# efm8ub1-kalypso-mezzanine-usb-interface-.net
KiCad netlist of a schematic drawn in EAGLE
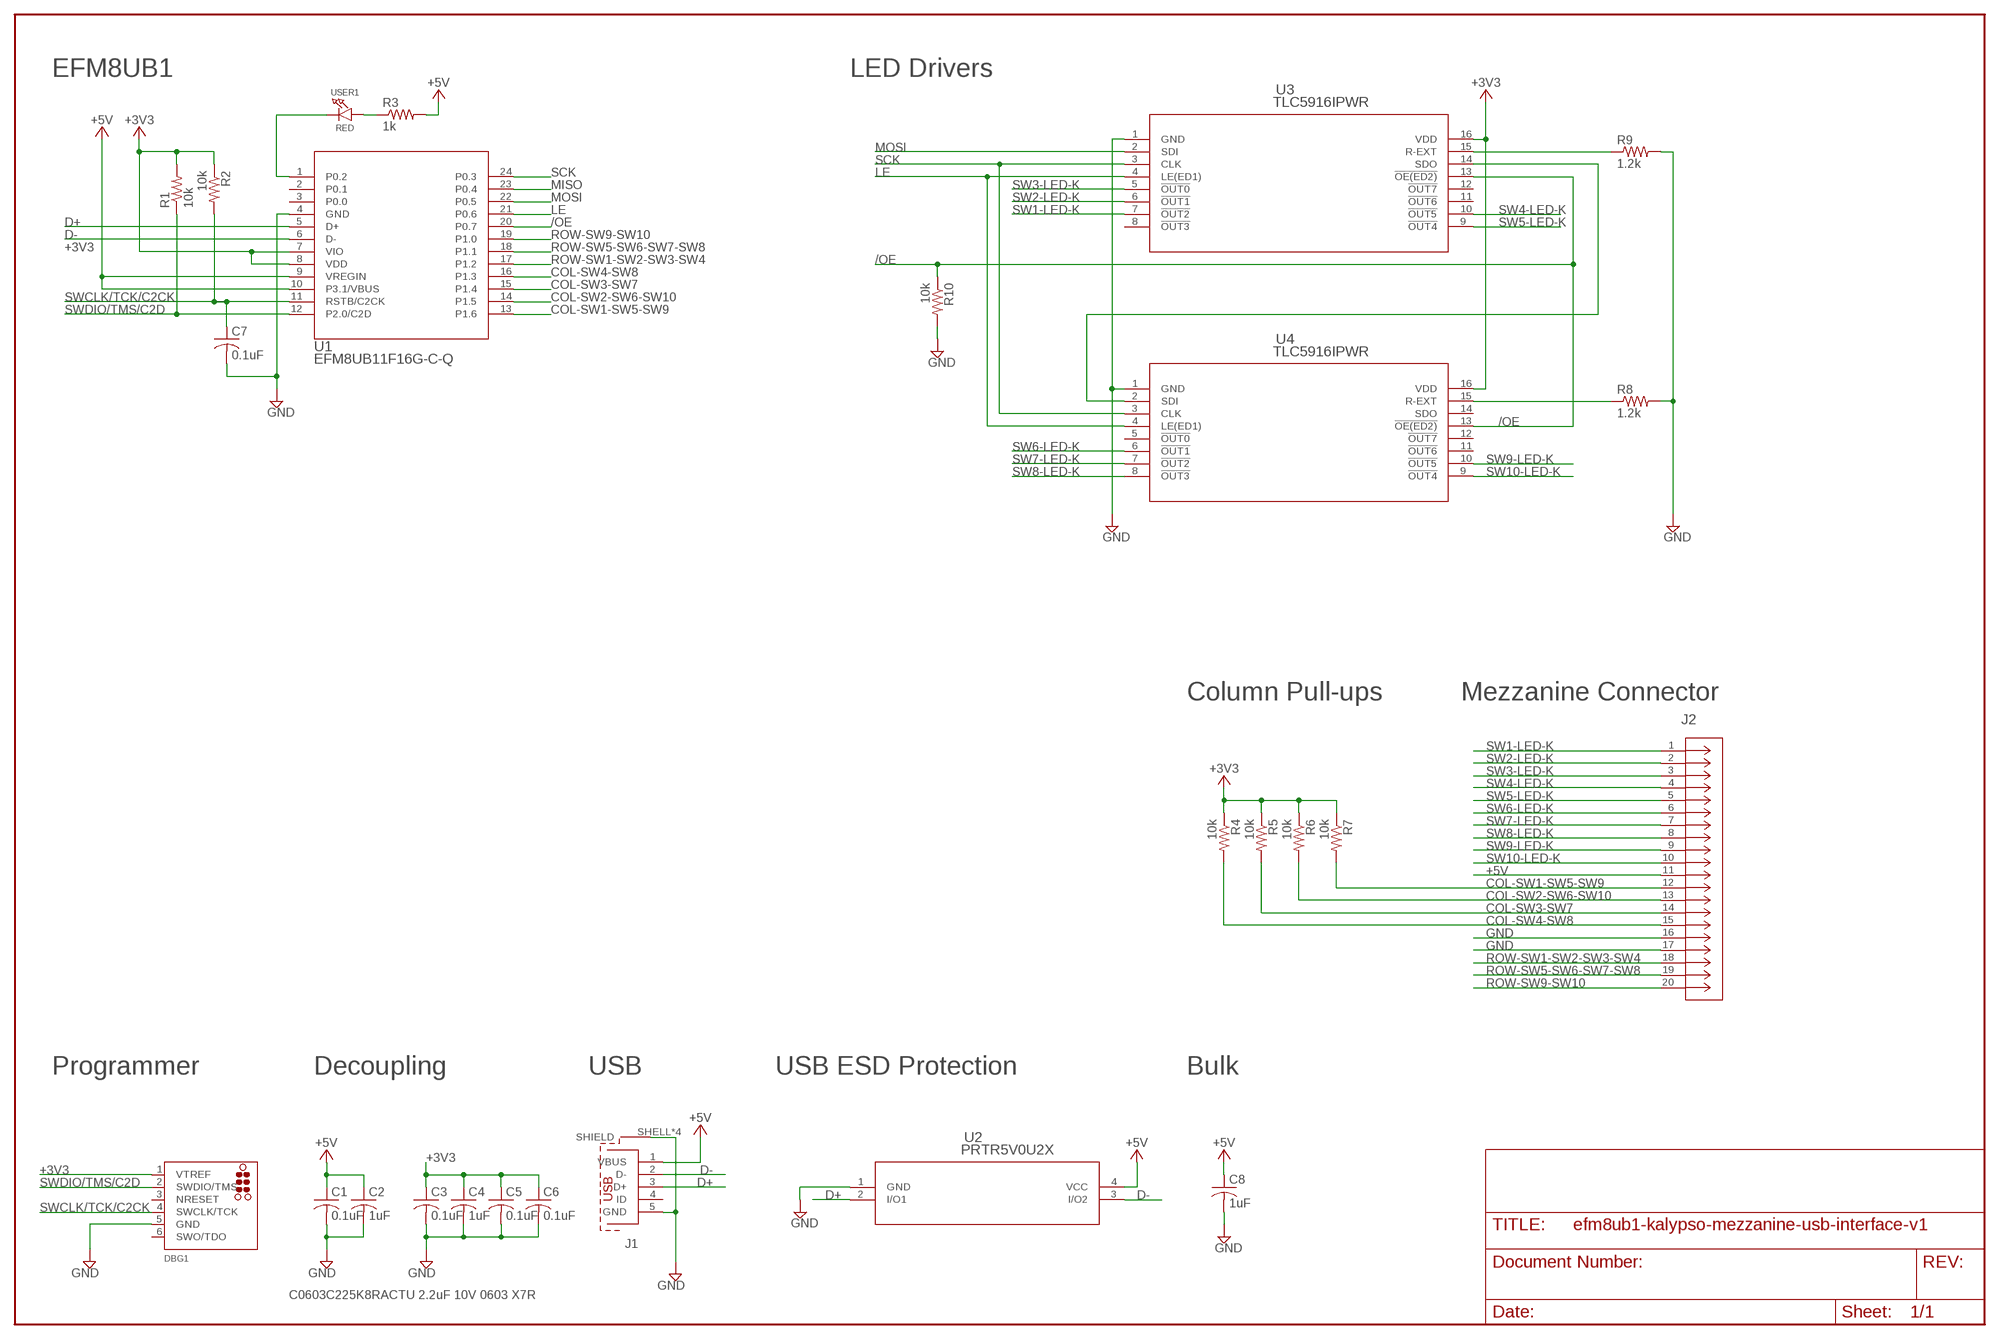
[diagram p0: schematic, sheet 1]

(export (version "E")
  (design (tool "Eeschema 10.0.6"))
  (components
    (comp (ref "C1")
      (value "0.1uF")
      (footprint "eagle-import:C0603")
      (libsource (lib "eagle-import") (part "C-USC0603"))
    )
    (comp (ref "C2")
      (value "1uF")
      (footprint "eagle-import:C0603")
      (libsource (lib "eagle-import") (part "C-USC0603"))
    )
    (comp (ref "C3")
      (value "0.1uF")
      (footprint "eagle-import:C0603")
      (libsource (lib "eagle-import") (part "C-USC0603"))
    )
    (comp (ref "C4")
      (value "1uF")
      (footprint "eagle-import:C0603")
      (libsource (lib "eagle-import") (part "C-USC0603"))
    )
    (comp (ref "C5")
      (value "0.1uF")
      (footprint "eagle-import:C0603")
      (libsource (lib "eagle-import") (part "C-USC0603"))
    )
    (comp (ref "C6")
      (value "0.1uF")
      (footprint "eagle-import:C0603")
      (libsource (lib "eagle-import") (part "C-USC0603"))
    )
    (comp (ref "C7")
      (value "0.1uF")
      (footprint "eagle-import:C0603")
      (libsource (lib "eagle-import") (part "C-USC0603"))
    )
    (comp (ref "C8")
      (value "1uF")
      (footprint "eagle-import:C1210")
      (libsource (lib "eagle-import") (part "C-USC1210"))
    )
    (comp (ref "DBG1")
      (value "TC2030-CTX-SWD")
      (footprint "eagle-import:TC2030-MCP-NL")
      (libsource (lib "eagle-import") (part "TC2030-CTX-SWD"))
    )
    (comp (ref "J1")
      (value "629105136821")
      (footprint "eagle-import:629105136821")
      (libsource (lib "eagle-import") (part "629105136821"))
    )
    (comp (ref "J2")
      (value "SLW20S-1C7LF")
      (footprint "eagle-import:CON20_1X20_UB_58JF_GLE")
      (libsource (lib "eagle-import") (part "SLW20S-1C7LF"))
    )
    (comp (ref "R1")
      (value "10k")
      (footprint "eagle-import:R0603")
      (libsource (lib "eagle-import") (part "R-US_R0603"))
    )
    (comp (ref "R2")
      (value "10k")
      (footprint "eagle-import:R0603")
      (libsource (lib "eagle-import") (part "R-US_R0603"))
    )
    (comp (ref "R3")
      (value "1k")
      (footprint "eagle-import:R0603")
      (libsource (lib "eagle-import") (part "R-US_R0603"))
    )
    (comp (ref "R4")
      (value "10k")
      (footprint "eagle-import:R0603")
      (libsource (lib "eagle-import") (part "R-US_R0603"))
    )
    (comp (ref "R5")
      (value "10k")
      (footprint "eagle-import:R0603")
      (libsource (lib "eagle-import") (part "R-US_R0603"))
    )
    (comp (ref "R6")
      (value "10k")
      (footprint "eagle-import:R0603")
      (libsource (lib "eagle-import") (part "R-US_R0603"))
    )
    (comp (ref "R7")
      (value "10k")
      (footprint "eagle-import:R0603")
      (libsource (lib "eagle-import") (part "R-US_R0603"))
    )
    (comp (ref "R8")
      (value "1.2k")
      (footprint "eagle-import:R0603")
      (libsource (lib "eagle-import") (part "R-US_R0603"))
    )
    (comp (ref "R9")
      (value "1.2k")
      (footprint "eagle-import:R0603")
      (libsource (lib "eagle-import") (part "R-US_R0603"))
    )
    (comp (ref "R10")
      (value "10k")
      (footprint "eagle-import:R0603")
      (libsource (lib "eagle-import") (part "R-US_R0603"))
    )
    (comp (ref "U1")
      (value "EFM8UB11F16G-C-Q")
      (footprint "eagle-import:QSOP24")
      (fields (field (name "MANUFACTURER_PART_NUMBER") "efm8ub11f16gbqsop24"))
      (libsource (lib "eagle-import") (part "EFM8UB11F16G-C-Q"))
    )
    (comp (ref "U2")
      (value "PRTR5V0U2X")
      (footprint "eagle-import:SOT143B")
      (libsource (lib "eagle-import") (part "PRTR5V0U2X"))
    )
    (comp (ref "U3")
      (value "TLC5916IPWR")
      (footprint "eagle-import:PW16_TEX")
      (fields (field (name "MANUFACTURER") "Texas Instruments"))
      (libsource (lib "eagle-import") (part "TLC5916IPWR"))
    )
    (comp (ref "U4")
      (value "TLC5916IPWR")
      (footprint "eagle-import:PW16_TEX")
      (fields (field (name "MANUFACTURER") "Texas Instruments"))
      (libsource (lib "eagle-import") (part "TLC5916IPWR"))
    )
    (comp (ref "USER1")
      (value "RED")
      (footprint "eagle-import:CHIPLED_0805_NOOUTLINE")
      (libsource (lib "eagle-import") (part "LED0805_NOOUTLINE"))
    )
  )
  (nets
    (net (code "1") (name "+3V3") (class "Default")
      (node (ref "C3") (pin "1") (pinfunction "1_1") (pintype "passive"))
      (node (ref "C4") (pin "1") (pinfunction "1_1") (pintype "passive"))
      (node (ref "C5") (pin "1") (pinfunction "1_1") (pintype "passive"))
      (node (ref "C6") (pin "1") (pinfunction "1_1") (pintype "passive"))
      (node (ref "DBG1") (pin "1") (pinfunction "VTREF_1") (pintype "passive"))
      (node (ref "R1") (pin "2") (pinfunction "2_2") (pintype "passive"))
      (node (ref "R2") (pin "1") (pinfunction "1_1") (pintype "passive"))
      (node (ref "R4") (pin "1") (pinfunction "1_1") (pintype "passive"))
      (node (ref "R5") (pin "1") (pinfunction "1_1") (pintype "passive"))
      (node (ref "R6") (pin "1") (pinfunction "1_1") (pintype "passive"))
      (node (ref "R7") (pin "1") (pinfunction "1_1") (pintype "passive"))
      (node (ref "U1") (pin "7") (pinfunction "VIO_7") (pintype "bidirectional"))
      (node (ref "U1") (pin "8") (pinfunction "VDD_8") (pintype "power_in"))
      (node (ref "U3") (pin "16") (pinfunction "VDD_16") (pintype "power_in"))
      (node (ref "U4") (pin "16") (pinfunction "VDD_16") (pintype "power_in"))
    )
    (net (code "2") (name "+5V") (class "Default")
      (node (ref "C1") (pin "1") (pinfunction "1_1") (pintype "passive"))
      (node (ref "C2") (pin "1") (pinfunction "1_1") (pintype "passive"))
      (node (ref "C8") (pin "1") (pinfunction "1_1") (pintype "passive"))
      (node (ref "J1") (pin "1") (pinfunction "VBUS_1") (pintype "passive"))
      (node (ref "J2") (pin "11") (pinfunction "11_11") (pintype "passive"))
      (node (ref "R3") (pin "2") (pinfunction "2_2") (pintype "passive"))
      (node (ref "U1") (pin "10") (pinfunction "P3.1/VBUS_10") (pintype "bidirectional"))
      (node (ref "U1") (pin "9") (pinfunction "VREGIN_9") (pintype "input"))
      (node (ref "U2") (pin "4") (pinfunction "VCC_4") (pintype "passive"))
    )
    (net (code "3") (name "/COL-SW1-SW5-SW9") (class "Default")
      (node (ref "J2") (pin "12") (pinfunction "12_12") (pintype "passive"))
      (node (ref "R7") (pin "2") (pinfunction "2_2") (pintype "passive"))
      (node (ref "U1") (pin "13") (pinfunction "P1.6_13") (pintype "bidirectional"))
    )
    (net (code "4") (name "/COL-SW2-SW6-SW10") (class "Default")
      (node (ref "J2") (pin "13") (pinfunction "13_13") (pintype "passive"))
      (node (ref "R6") (pin "2") (pinfunction "2_2") (pintype "passive"))
      (node (ref "U1") (pin "14") (pinfunction "P1.5_14") (pintype "bidirectional"))
    )
    (net (code "5") (name "/COL-SW3-SW7") (class "Default")
      (node (ref "J2") (pin "14") (pinfunction "14_14") (pintype "passive"))
      (node (ref "R5") (pin "2") (pinfunction "2_2") (pintype "passive"))
      (node (ref "U1") (pin "15") (pinfunction "P1.4_15") (pintype "bidirectional"))
    )
    (net (code "6") (name "/COL-SW4-SW8") (class "Default")
      (node (ref "J2") (pin "15") (pinfunction "15_15") (pintype "passive"))
      (node (ref "R4") (pin "2") (pinfunction "2_2") (pintype "passive"))
      (node (ref "U1") (pin "16") (pinfunction "P1.3_16") (pintype "bidirectional"))
    )
    (net (code "7") (name "/D+") (class "Default")
      (node (ref "J1") (pin "3") (pinfunction "D+_3") (pintype "passive"))
      (node (ref "U1") (pin "5") (pinfunction "D+_5") (pintype "bidirectional"))
      (node (ref "U2") (pin "2") (pinfunction "I/O1_2") (pintype "passive"))
    )
    (net (code "8") (name "/D-") (class "Default")
      (node (ref "J1") (pin "2") (pinfunction "D-_2") (pintype "passive"))
      (node (ref "U1") (pin "6") (pinfunction "D-_6") (pintype "bidirectional"))
      (node (ref "U2") (pin "3") (pinfunction "I/O2_3") (pintype "passive"))
    )
    (net (code "9") (name "/LE") (class "Default")
      (node (ref "U1") (pin "21") (pinfunction "P0.6_21") (pintype "bidirectional"))
      (node (ref "U3") (pin "4") (pinfunction "LE(ED1)_4") (pintype "input"))
      (node (ref "U4") (pin "4") (pinfunction "LE(ED1)_4") (pintype "input"))
    )
    (net (code "10") (name "/MISO") (class "Default")
      (node (ref "U1") (pin "23") (pinfunction "P0.4_23") (pintype "bidirectional"))
    )
    (net (code "11") (name "/MOSI") (class "Default")
      (node (ref "U1") (pin "22") (pinfunction "P0.5_22") (pintype "bidirectional"))
      (node (ref "U3") (pin "2") (pinfunction "SDI_2") (pintype "input"))
    )
    (net (code "12") (name "/NRESET") (class "Default")
      (node (ref "DBG1") (pin "3") (pinfunction "NRESET_3") (pintype "power_in"))
    )
    (net (code "13") (name "/ROW-SW1-SW2-SW3-SW4") (class "Default")
      (node (ref "J2") (pin "18") (pinfunction "18_18") (pintype "passive"))
      (node (ref "U1") (pin "17") (pinfunction "P1.2_17") (pintype "bidirectional"))
    )
    (net (code "14") (name "/ROW-SW5-SW6-SW7-SW8") (class "Default")
      (node (ref "J2") (pin "19") (pinfunction "19_19") (pintype "passive"))
      (node (ref "U1") (pin "18") (pinfunction "P1.1_18") (pintype "bidirectional"))
    )
    (net (code "15") (name "/ROW-SW9-SW10") (class "Default")
      (node (ref "J2") (pin "20") (pinfunction "20_20") (pintype "passive"))
      (node (ref "U1") (pin "19") (pinfunction "P1.0_19") (pintype "bidirectional"))
    )
    (net (code "16") (name "/SCK") (class "Default")
      (node (ref "U1") (pin "24") (pinfunction "P0.3_24") (pintype "bidirectional"))
      (node (ref "U3") (pin "3") (pinfunction "CLK_3") (pintype "input"))
      (node (ref "U4") (pin "3") (pinfunction "CLK_3") (pintype "input"))
    )
    (net (code "17") (name "/SW1-LED-K") (class "Default")
      (node (ref "J2") (pin "1") (pinfunction "1_1") (pintype "passive"))
      (node (ref "U3") (pin "7") (pinfunction "~{OUT2}_7") (pintype "output"))
    )
    (net (code "18") (name "/SW2-LED-K") (class "Default")
      (node (ref "J2") (pin "2") (pinfunction "2_2") (pintype "passive"))
      (node (ref "U3") (pin "6") (pinfunction "~{OUT1}_6") (pintype "output"))
    )
    (net (code "19") (name "/SW3-LED-K") (class "Default")
      (node (ref "J2") (pin "3") (pinfunction "3_3") (pintype "passive"))
      (node (ref "U3") (pin "5") (pinfunction "~{OUT0}_5") (pintype "output"))
    )
    (net (code "20") (name "/SW4-LED-K") (class "Default")
      (node (ref "J2") (pin "4") (pinfunction "4_4") (pintype "passive"))
      (node (ref "U3") (pin "10") (pinfunction "~{OUT5}_10") (pintype "output"))
    )
    (net (code "21") (name "/SW5-LED-K") (class "Default")
      (node (ref "J2") (pin "5") (pinfunction "5_5") (pintype "passive"))
      (node (ref "U3") (pin "9") (pinfunction "~{OUT4}_9") (pintype "output"))
    )
    (net (code "22") (name "/SW6-LED-K") (class "Default")
      (node (ref "J2") (pin "6") (pinfunction "6_6") (pintype "passive"))
      (node (ref "U4") (pin "6") (pinfunction "~{OUT1}_6") (pintype "output"))
    )
    (net (code "23") (name "/SW7-LED-K") (class "Default")
      (node (ref "J2") (pin "7") (pinfunction "7_7") (pintype "passive"))
      (node (ref "U4") (pin "7") (pinfunction "~{OUT2}_7") (pintype "output"))
    )
    (net (code "24") (name "/SW8-LED-K") (class "Default")
      (node (ref "J2") (pin "8") (pinfunction "8_8") (pintype "passive"))
      (node (ref "U4") (pin "8") (pinfunction "~{OUT3}_8") (pintype "output"))
    )
    (net (code "25") (name "/SW9-LED-K") (class "Default")
      (node (ref "J2") (pin "9") (pinfunction "9_9") (pintype "passive"))
      (node (ref "U4") (pin "10") (pinfunction "~{OUT5}_10") (pintype "output"))
    )
    (net (code "26") (name "/SW10-LED-K") (class "Default")
      (node (ref "J2") (pin "10") (pinfunction "10_10") (pintype "passive"))
      (node (ref "U4") (pin "9") (pinfunction "~{OUT4}_9") (pintype "output"))
    )
    (net (code "27") (name "/SWCLK{slash}TCK{slash}C2CK") (class "Default")
      (node (ref "C7") (pin "1") (pinfunction "1_1") (pintype "passive"))
      (node (ref "DBG1") (pin "4") (pinfunction "SWCLK/TCK_4") (pintype "bidirectional"))
      (node (ref "R2") (pin "2") (pinfunction "2_2") (pintype "passive"))
      (node (ref "U1") (pin "11") (pinfunction "RSTB/C2CK_11") (pintype "bidirectional"))
    )
    (net (code "28") (name "/SWDIO{slash}TMS{slash}C2D") (class "Default")
      (node (ref "DBG1") (pin "2") (pinfunction "SWDIO/TMS_2") (pintype "power_in"))
      (node (ref "R1") (pin "1") (pinfunction "1_1") (pintype "passive"))
      (node (ref "U1") (pin "12") (pinfunction "P2.0/C2D_12") (pintype "bidirectional"))
    )
    (net (code "29") (name "/{slash}OE") (class "Default")
      (node (ref "R10") (pin "1") (pinfunction "1_1") (pintype "passive"))
      (node (ref "U1") (pin "20") (pinfunction "P0.7_20") (pintype "bidirectional"))
      (node (ref "U3") (pin "13") (pinfunction "~{OE(ED2})_13") (pintype "output"))
      (node (ref "U4") (pin "13") (pinfunction "~{OE(ED2})_13") (pintype "output"))
    )
    (net (code "30") (name "GND") (class "Default")
      (node (ref "C1") (pin "2") (pinfunction "2_2") (pintype "passive"))
      (node (ref "C2") (pin "2") (pinfunction "2_2") (pintype "passive"))
      (node (ref "C3") (pin "2") (pinfunction "2_2") (pintype "passive"))
      (node (ref "C4") (pin "2") (pinfunction "2_2") (pintype "passive"))
      (node (ref "C5") (pin "2") (pinfunction "2_2") (pintype "passive"))
      (node (ref "C6") (pin "2") (pinfunction "2_2") (pintype "passive"))
      (node (ref "C7") (pin "2") (pinfunction "2_2") (pintype "passive"))
      (node (ref "C8") (pin "2") (pinfunction "2_2") (pintype "passive"))
      (node (ref "DBG1") (pin "5") (pinfunction "GND_5") (pintype "output"))
      (node (ref "J1") (pin "5") (pinfunction "GND_5") (pintype "passive"))
      (node (ref "J1") (pin "SHELL") (pinfunction "SHIELD_SHELL") (pintype "passive"))
      (node (ref "J1") (pin "SHELL1") (pinfunction "SHIELD_SHELL1") (pintype "passive"))
      (node (ref "J1") (pin "SHELL2") (pinfunction "SHIELD_SHELL2") (pintype "passive"))
      (node (ref "J1") (pin "SHELL3") (pinfunction "SHIELD_SHELL3") (pintype "passive"))
      (node (ref "J2") (pin "16") (pinfunction "16_16") (pintype "passive"))
      (node (ref "J2") (pin "17") (pinfunction "17_17") (pintype "passive"))
      (node (ref "R10") (pin "2") (pinfunction "2_2") (pintype "passive"))
      (node (ref "R8") (pin "2") (pinfunction "2_2") (pintype "passive"))
      (node (ref "R9") (pin "2") (pinfunction "2_2") (pintype "passive"))
      (node (ref "U1") (pin "4") (pinfunction "GND_4") (pintype "power_in"))
      (node (ref "U2") (pin "1") (pinfunction "GND_1") (pintype "passive"))
      (node (ref "U3") (pin "1") (pinfunction "GND_1") (pintype "power_in"))
      (node (ref "U4") (pin "1") (pinfunction "GND_1") (pintype "power_in"))
    )
    (net (code "31") (name "Net-(R3-Pad1)") (class "Default")
      (node (ref "R3") (pin "1") (pinfunction "1_1") (pintype "passive"))
      (node (ref "USER1") (pin "A") (pinfunction "A_A") (pintype "passive"))
    )
    (net (code "32") (name "Net-(U1-P0.2)") (class "Default")
      (node (ref "U1") (pin "1") (pinfunction "P0.2_1") (pintype "bidirectional"))
      (node (ref "USER1") (pin "C") (pinfunction "C_C") (pintype "passive"))
    )
    (net (code "33") (name "Net-(U3-R-EXT)") (class "Default")
      (node (ref "R9") (pin "1") (pinfunction "1_1") (pintype "passive"))
      (node (ref "U3") (pin "15") (pinfunction "R-EXT_15") (pintype "passive"))
    )
    (net (code "34") (name "Net-(U3-SDO)") (class "Default")
      (node (ref "U3") (pin "14") (pinfunction "SDO_14") (pintype "output"))
      (node (ref "U4") (pin "2") (pinfunction "SDI_2") (pintype "input"))
    )
    (net (code "35") (name "Net-(U4-R-EXT)") (class "Default")
      (node (ref "R8") (pin "1") (pinfunction "1_1") (pintype "passive"))
      (node (ref "U4") (pin "15") (pinfunction "R-EXT_15") (pintype "passive"))
    )
    (net (code "36") (name "unconnected-(DBG1-SWO{slash}TDO-Pad6)") (class "Default")
      (node (ref "DBG1") (pin "6") (pinfunction "SWO/TDO_6") (pintype "bidirectional"))
    )
    (net (code "37") (name "unconnected-(J1-ID-Pad4)") (class "Default")
      (node (ref "J1") (pin "4") (pinfunction "ID_4") (pintype "passive"))
    )
    (net (code "38") (name "unconnected-(U1-P0.0-Pad3)") (class "Default")
      (node (ref "U1") (pin "3") (pinfunction "P0.0_3") (pintype "bidirectional"))
    )
    (net (code "39") (name "unconnected-(U1-P0.1-Pad2)") (class "Default")
      (node (ref "U1") (pin "2") (pinfunction "P0.1_2") (pintype "bidirectional"))
    )
    (net (code "40") (name "unconnected-(U3-~{OUT3}-Pad8)") (class "Default")
      (node (ref "U3") (pin "8") (pinfunction "~{OUT3}_8") (pintype "output"))
    )
    (net (code "41") (name "unconnected-(U3-~{OUT6}-Pad11)") (class "Default")
      (node (ref "U3") (pin "11") (pinfunction "~{OUT6}_11") (pintype "output"))
    )
    (net (code "42") (name "unconnected-(U3-~{OUT7}-Pad12)") (class "Default")
      (node (ref "U3") (pin "12") (pinfunction "~{OUT7}_12") (pintype "output"))
    )
    (net (code "43") (name "unconnected-(U4-SDO-Pad14)") (class "Default")
      (node (ref "U4") (pin "14") (pinfunction "SDO_14") (pintype "output"))
    )
    (net (code "44") (name "unconnected-(U4-~{OUT0}-Pad5)") (class "Default")
      (node (ref "U4") (pin "5") (pinfunction "~{OUT0}_5") (pintype "output"))
    )
    (net (code "45") (name "unconnected-(U4-~{OUT6}-Pad11)") (class "Default")
      (node (ref "U4") (pin "11") (pinfunction "~{OUT6}_11") (pintype "output"))
    )
    (net (code "46") (name "unconnected-(U4-~{OUT7}-Pad12)") (class "Default")
      (node (ref "U4") (pin "12") (pinfunction "~{OUT7}_12") (pintype "output"))
    )
  )
)
